# polar_lcd.net
KiCad netlist of a schematic drawn in EAGLE
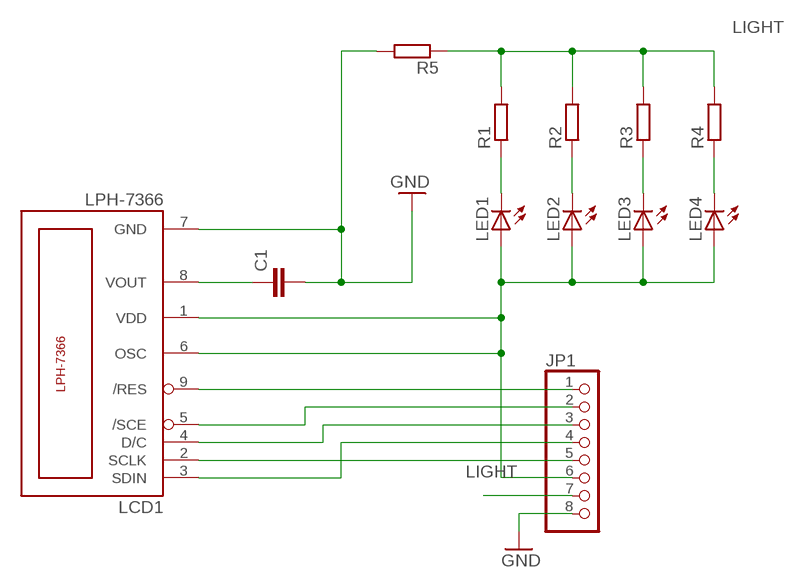
[diagram p0: schematic, sheet 1]

(export (version "E")
  (design (tool "Eeschema 10.0.6"))
  (components
    (comp (ref "C1")
      (value "C-EUC0805")
      (footprint "eagle-import:C0805")
      (libsource (lib "eagle-import") (part "C-EUC0805"))
    )
    (comp (ref "JP1")
      (value "PINHD-1X8")
      (footprint "eagle-import:1X08")
      (libsource (lib "eagle-import") (part "PINHD-1X8"))
    )
    (comp (ref "LCD1")
      (value "LPH-7366")
      (footprint "eagle-import:LPH-7366")
      (libsource (lib "eagle-import") (part "LPH-7366"))
    )
    (comp (ref "LED1")
      (value "LEDSMT1206")
      (footprint "eagle-import:1206")
      (libsource (lib "eagle-import") (part "LEDSMT1206"))
    )
    (comp (ref "LED2")
      (value "LEDSMT1206")
      (footprint "eagle-import:1206")
      (libsource (lib "eagle-import") (part "LEDSMT1206"))
    )
    (comp (ref "LED3")
      (value "LEDSMT1206")
      (footprint "eagle-import:1206")
      (libsource (lib "eagle-import") (part "LEDSMT1206"))
    )
    (comp (ref "LED4")
      (value "LEDSMT1206")
      (footprint "eagle-import:1206")
      (libsource (lib "eagle-import") (part "LEDSMT1206"))
    )
    (comp (ref "R1")
      (value "R-EU_R0805")
      (footprint "eagle-import:R0805")
      (libsource (lib "eagle-import") (part "R-EU_R0805"))
    )
    (comp (ref "R2")
      (value "R-EU_R0805")
      (footprint "eagle-import:R0805")
      (libsource (lib "eagle-import") (part "R-EU_R0805"))
    )
    (comp (ref "R3")
      (value "R-EU_R0805")
      (footprint "eagle-import:R0805")
      (libsource (lib "eagle-import") (part "R-EU_R0805"))
    )
    (comp (ref "R4")
      (value "R-EU_R0805")
      (footprint "eagle-import:R0805")
      (libsource (lib "eagle-import") (part "R-EU_R0805"))
    )
    (comp (ref "R5")
      (value "R-EU_R0805")
      (footprint "eagle-import:R0805")
      (libsource (lib "eagle-import") (part "R-EU_R0805"))
    )
  )
  (nets
    (net (code "1") (name "/LIGHT") (class "Default")
      (node (ref "JP1") (pin "7") (pinfunction "7_7") (pintype "passive"))
      (node (ref "R1") (pin "2") (pinfunction "2_2") (pintype "passive"))
      (node (ref "R2") (pin "2") (pinfunction "2_2") (pintype "passive"))
      (node (ref "R3") (pin "2") (pinfunction "2_2") (pintype "passive"))
      (node (ref "R4") (pin "2") (pinfunction "2_2") (pintype "passive"))
      (node (ref "R5") (pin "1") (pinfunction "1_1") (pintype "passive"))
    )
    (net (code "2") (name "GND") (class "Default")
      (node (ref "C1") (pin "2") (pinfunction "2_2") (pintype "passive"))
      (node (ref "JP1") (pin "8") (pinfunction "8_8") (pintype "passive"))
      (node (ref "LCD1") (pin "7") (pinfunction "GND_7") (pintype "power_in"))
      (node (ref "R5") (pin "2") (pinfunction "2_2") (pintype "passive"))
    )
    (net (code "3") (name "Net-(LCD1-D{slash}C)") (class "Default")
      (node (ref "JP1") (pin "3") (pinfunction "3_3") (pintype "passive"))
      (node (ref "LCD1") (pin "4") (pinfunction "D/C_4") (pintype "input"))
    )
    (net (code "4") (name "Net-(LCD1-OSC)") (class "Default")
      (node (ref "JP1") (pin "6") (pinfunction "6_6") (pintype "passive"))
      (node (ref "LCD1") (pin "1") (pinfunction "VDD_1") (pintype "power_in"))
      (node (ref "LCD1") (pin "6") (pinfunction "OSC_6") (pintype "passive"))
      (node (ref "LED1") (pin "A") (pinfunction "A_A") (pintype "passive"))
      (node (ref "LED2") (pin "A") (pinfunction "A_A") (pintype "passive"))
      (node (ref "LED3") (pin "A") (pinfunction "A_A") (pintype "passive"))
      (node (ref "LED4") (pin "A") (pinfunction "A_A") (pintype "passive"))
    )
    (net (code "5") (name "Net-(LCD1-SCLK)") (class "Default")
      (node (ref "JP1") (pin "5") (pinfunction "5_5") (pintype "passive"))
      (node (ref "LCD1") (pin "2") (pinfunction "SCLK_2") (pintype "input"))
    )
    (net (code "6") (name "Net-(LCD1-SDIN)") (class "Default")
      (node (ref "JP1") (pin "4") (pinfunction "4_4") (pintype "passive"))
      (node (ref "LCD1") (pin "3") (pinfunction "SDIN_3") (pintype "input"))
    )
    (net (code "7") (name "Net-(LCD1-VOUT)") (class "Default")
      (node (ref "C1") (pin "1") (pinfunction "1_1") (pintype "passive"))
      (node (ref "LCD1") (pin "8") (pinfunction "VOUT_8") (pintype "passive"))
    )
    (net (code "8") (name "Net-(LCD1-{slash}RES)") (class "Default")
      (node (ref "JP1") (pin "1") (pinfunction "1_1") (pintype "passive"))
      (node (ref "LCD1") (pin "9") (pinfunction "/RES_9") (pintype "input"))
    )
    (net (code "9") (name "Net-(LCD1-{slash}SCE)") (class "Default")
      (node (ref "JP1") (pin "2") (pinfunction "2_2") (pintype "passive"))
      (node (ref "LCD1") (pin "5") (pinfunction "/SCE_5") (pintype "input"))
    )
    (net (code "10") (name "Net-(LED1-PadC)") (class "Default")
      (node (ref "LED1") (pin "C") (pinfunction "C_C") (pintype "passive"))
      (node (ref "R1") (pin "1") (pinfunction "1_1") (pintype "passive"))
    )
    (net (code "11") (name "Net-(LED2-PadC)") (class "Default")
      (node (ref "LED2") (pin "C") (pinfunction "C_C") (pintype "passive"))
      (node (ref "R2") (pin "1") (pinfunction "1_1") (pintype "passive"))
    )
    (net (code "12") (name "Net-(LED3-PadC)") (class "Default")
      (node (ref "LED3") (pin "C") (pinfunction "C_C") (pintype "passive"))
      (node (ref "R3") (pin "1") (pinfunction "1_1") (pintype "passive"))
    )
    (net (code "13") (name "Net-(LED4-PadC)") (class "Default")
      (node (ref "LED4") (pin "C") (pinfunction "C_C") (pintype "passive"))
      (node (ref "R4") (pin "1") (pinfunction "1_1") (pintype "passive"))
    )
  )
)
